# DAPLink.net
KiCad netlist of a schematic drawn in EasyEDA Pro
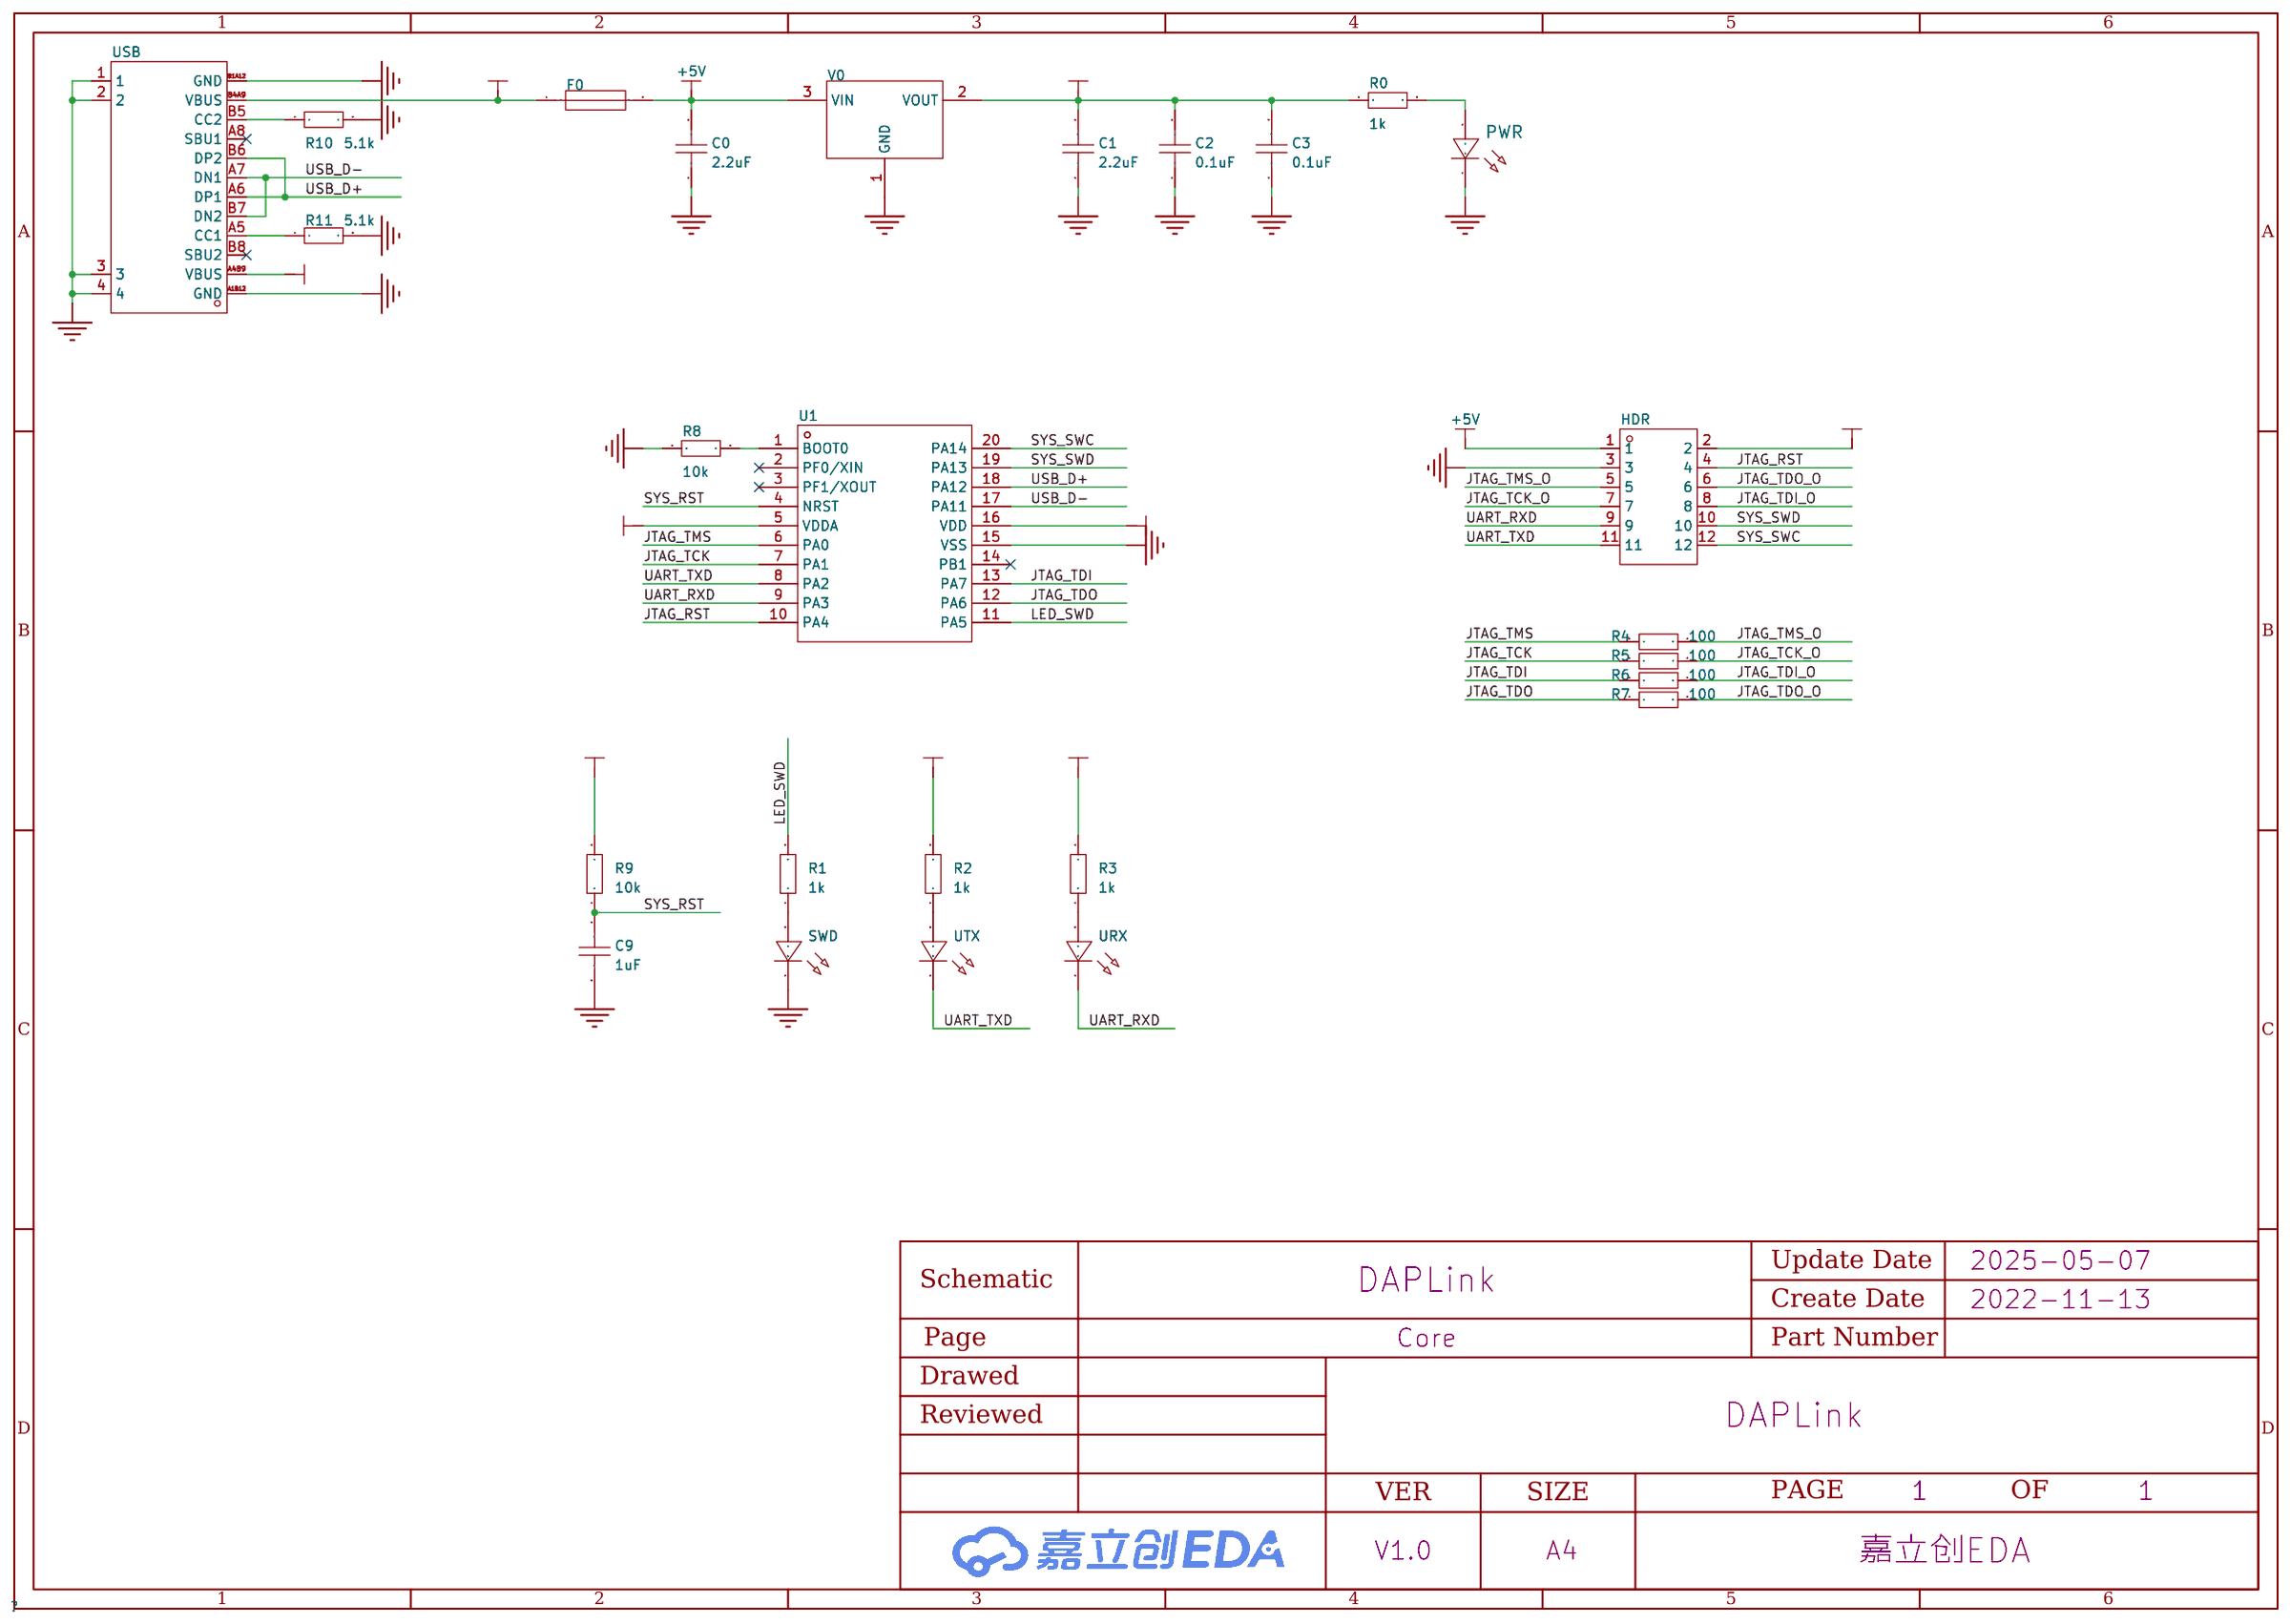
[diagram p0: schematic sheet]

(export (version "E")
  (design (tool "Eeschema 10.0.6"))
  (components
    (comp (ref "C0")
      (value "2.2uF")
      (footprint "easyedapro:C0603")
      (description "容值:100nF;精度:±10%;额定电压:50V;温度系数:X7R;")
      (libsource (lib "easyedapro") (part "C1210X7R475K630NT"))
    )
    (comp (ref "C1")
      (value "2.2uF")
      (footprint "easyedapro:C0603")
      (description "容值:100nF;精度:±10%;额定电压:50V;温度系数:X7R;")
      (libsource (lib "easyedapro") (part "C1210X7R475K630NT"))
    )
    (comp (ref "C2")
      (value "0.1uF")
      (footprint "easyedapro:C0603")
      (description "容值:100nF;精度:±10%;额定电压:50V;温度系数:X7R;")
      (libsource (lib "easyedapro") (part "C1210X7R475K630NT"))
    )
    (comp (ref "C3")
      (value "0.1uF")
      (footprint "easyedapro:C0603")
      (description "容值:100nF;精度:±10%;额定电压:50V;温度系数:X7R;")
      (libsource (lib "easyedapro") (part "C1210X7R475K630NT"))
    )
    (comp (ref "C9")
      (value "1uF")
      (footprint "easyedapro:C0603")
      (description "容值:100nF;精度:±10%;额定电压:50V;温度系数:X7R;")
      (libsource (lib "easyedapro") (part "C1210X7R475K630NT"))
    )
    (comp (ref "F0")
      (value "JK-nSMD050-30")
      (footprint "easyedapro:F1206")
      (description "耐压:30V;最大电流:100A;保持电流(Ih):500mA;跳闸电流:1A;")
      (fields (field (name "Manufacturer") "JK(金科)"))
      (libsource (lib "easyedapro") (part "JK-NSMD050-30V"))
    )
    (comp (ref "HDR")
      (value "~")
      (footprint "easyedapro:HDR-SMD_2X6P-P2.54")
      (libsource (lib "easyedapro") (part "HDR-M-2.54_2x6"))
    )
    (comp (ref "PWR")
      (value "~")
      (footprint "easyedapro:LED_0603")
      (libsource (lib "easyedapro") (part "LED_R"))
    )
    (comp (ref "R0") (value "1k") (footprint "easyedapro:R0603") (libsource (lib "easyedapro") (part "电阻")))
    (comp (ref "R1") (value "1k") (footprint "easyedapro:R0603") (libsource (lib "easyedapro") (part "电阻")))
    (comp (ref "R2") (value "1k") (footprint "easyedapro:R0603") (libsource (lib "easyedapro") (part "电阻")))
    (comp (ref "R3") (value "1k") (footprint "easyedapro:R0603") (libsource (lib "easyedapro") (part "电阻")))
    (comp (ref "R4") (value "100") (footprint "easyedapro:R0603") (libsource (lib "easyedapro") (part "电阻")))
    (comp (ref "R5") (value "100") (footprint "easyedapro:R0603") (libsource (lib "easyedapro") (part "电阻")))
    (comp (ref "R6") (value "100") (footprint "easyedapro:R0603") (libsource (lib "easyedapro") (part "电阻")))
    (comp (ref "R7") (value "100") (footprint "easyedapro:R0603") (libsource (lib "easyedapro") (part "电阻")))
    (comp (ref "R8") (value "10k") (footprint "easyedapro:R0603") (libsource (lib "easyedapro") (part "电阻")))
    (comp (ref "R9") (value "10k") (footprint "easyedapro:R0603") (libsource (lib "easyedapro") (part "电阻")))
    (comp (ref "R10")
      (value "5.1k")
      (footprint "easyedapro:R0603")
      (libsource (lib "easyedapro") (part "电阻"))
    )
    (comp (ref "R11")
      (value "5.1k")
      (footprint "easyedapro:R0603")
      (libsource (lib "easyedapro") (part "电阻"))
    )
    (comp (ref "SWD")
      (value "~")
      (footprint "easyedapro:LED_0603")
      (libsource (lib "easyedapro") (part "LED_B"))
    )
    (comp (ref "U1")
      (value "~")
      (footprint "easyedapro:TSSOP-20_L6.5-W4.4-P0.65-LS6.4-BL")
      (libsource (lib "easyedapro") (part "AT32F425F8"))
    )
    (comp (ref "URX")
      (value "~")
      (footprint "easyedapro:LED_0603")
      (libsource (lib "easyedapro") (part "LED_G"))
    )
    (comp (ref "USB")
      (value "USB-TYPE-C-017")
      (footprint "easyedapro:USB-TYPE-C-SMD_C9900008089")
      (description "连接器类型:Type-C;标准:-;公母:母座;触点数量:16;端口数量:1;安装方式:卧贴;额定电流 - 电源:3A;工作温度范围:-25~+85;")
      (fields (field (name "Manufacturer") "DEALON(德艺隆)"))
      (libsource (lib "easyedapro") (part "USB-TYPE-C-017"))
    )
    (comp (ref "UTX")
      (value "~")
      (footprint "easyedapro:LED_0603")
      (libsource (lib "easyedapro") (part "LED_G"))
    )
    (comp (ref "V0")
      (value "HT7233")
      (footprint "easyedapro:SOT-23-3_L2.9-W1.6-P1.90-LS2.8-BR")
      (fields (field (name "Manufacturer") "HOLTEK(台湾合泰/盛群)"))
      (libsource (lib "easyedapro") (part "HT7233"))
    )
  )
  (nets
    (net (code "1") (name "+3.3V") (class "Default")
      (node (ref "C1") (pin "2") (pinfunction "2_2") (pintype "input"))
      (node (ref "C2") (pin "2") (pinfunction "2_2") (pintype "input"))
      (node (ref "C3") (pin "2") (pinfunction "2_2") (pintype "input"))
      (node (ref "HDR") (pin "2") (pinfunction "2_2") (pintype "input"))
      (node (ref "R0") (pin "1") (pinfunction "1_1") (pintype "input"))
      (node (ref "R2") (pin "2") (pinfunction "2_2") (pintype "input"))
      (node (ref "R3") (pin "2") (pinfunction "2_2") (pintype "input"))
      (node (ref "R9") (pin "2") (pinfunction "2_2") (pintype "input"))
      (node (ref "U1") (pin "16") (pinfunction "VDD_16") (pintype "input"))
      (node (ref "U1") (pin "5") (pinfunction "VDDA_5") (pintype "input"))
      (node (ref "V0") (pin "2") (pinfunction "VOUT_2") (pintype "unspecified"))
    )
    (net (code "2") (name "+5V") (class "Default")
      (node (ref "C0") (pin "2") (pinfunction "2_2") (pintype "input"))
      (node (ref "F0") (pin "2") (pinfunction "2_2") (pintype "unspecified"))
      (node (ref "HDR") (pin "1") (pinfunction "1_1") (pintype "input"))
      (node (ref "V0") (pin "3") (pinfunction "VIN_3") (pintype "unspecified"))
    )
    (net (code "3") (name "/JTAG_RST") (class "Default")
      (node (ref "HDR") (pin "4") (pinfunction "4_4") (pintype "input"))
      (node (ref "U1") (pin "10") (pinfunction "PA4_10") (pintype "input"))
    )
    (net (code "4") (name "/JTAG_TCK") (class "Default")
      (node (ref "R5") (pin "1") (pinfunction "1_1") (pintype "input"))
      (node (ref "U1") (pin "7") (pinfunction "PA1_7") (pintype "input"))
    )
    (net (code "5") (name "/JTAG_TCK_O") (class "Default")
      (node (ref "HDR") (pin "7") (pinfunction "7_7") (pintype "input"))
      (node (ref "R5") (pin "2") (pinfunction "2_2") (pintype "input"))
    )
    (net (code "6") (name "/JTAG_TDI") (class "Default")
      (node (ref "R6") (pin "1") (pinfunction "1_1") (pintype "input"))
      (node (ref "U1") (pin "13") (pinfunction "PA7_13") (pintype "input"))
    )
    (net (code "7") (name "/JTAG_TDI_O") (class "Default")
      (node (ref "HDR") (pin "8") (pinfunction "8_8") (pintype "input"))
      (node (ref "R6") (pin "2") (pinfunction "2_2") (pintype "input"))
    )
    (net (code "8") (name "/JTAG_TDO") (class "Default")
      (node (ref "R7") (pin "1") (pinfunction "1_1") (pintype "input"))
      (node (ref "U1") (pin "12") (pinfunction "PA6_12") (pintype "input"))
    )
    (net (code "9") (name "/JTAG_TDO_O") (class "Default")
      (node (ref "HDR") (pin "6") (pinfunction "6_6") (pintype "input"))
      (node (ref "R7") (pin "2") (pinfunction "2_2") (pintype "input"))
    )
    (net (code "10") (name "/JTAG_TMS") (class "Default")
      (node (ref "R4") (pin "1") (pinfunction "1_1") (pintype "input"))
      (node (ref "U1") (pin "6") (pinfunction "PA0_6") (pintype "input"))
    )
    (net (code "11") (name "/JTAG_TMS_O") (class "Default")
      (node (ref "HDR") (pin "5") (pinfunction "5_5") (pintype "input"))
      (node (ref "R4") (pin "2") (pinfunction "2_2") (pintype "input"))
    )
    (net (code "12") (name "/LED_SWD") (class "Default")
      (node (ref "R1") (pin "2") (pinfunction "2_2") (pintype "input"))
      (node (ref "U1") (pin "11") (pinfunction "PA5_11") (pintype "input"))
    )
    (net (code "13") (name "/SYS_RST") (class "Default")
      (node (ref "C9") (pin "1") (pinfunction "1_1") (pintype "input"))
      (node (ref "R9") (pin "1") (pinfunction "1_1") (pintype "input"))
      (node (ref "U1") (pin "4") (pinfunction "NRST_4") (pintype "input"))
    )
    (net (code "14") (name "/SYS_SWC") (class "Default")
      (node (ref "HDR") (pin "12") (pinfunction "12_12") (pintype "input"))
      (node (ref "U1") (pin "20") (pinfunction "PA14_20") (pintype "input"))
    )
    (net (code "15") (name "/SYS_SWD") (class "Default")
      (node (ref "HDR") (pin "10") (pinfunction "10_10") (pintype "input"))
      (node (ref "U1") (pin "19") (pinfunction "PA13_19") (pintype "input"))
    )
    (net (code "16") (name "/UART_RXD") (class "Default")
      (node (ref "HDR") (pin "9") (pinfunction "9_9") (pintype "input"))
      (node (ref "U1") (pin "9") (pinfunction "PA3_9") (pintype "input"))
      (node (ref "URX") (pin "1") (pinfunction "C_1") (pintype "input"))
    )
    (net (code "17") (name "/UART_TXD") (class "Default")
      (node (ref "HDR") (pin "11") (pinfunction "11_11") (pintype "input"))
      (node (ref "U1") (pin "8") (pinfunction "PA2_8") (pintype "input"))
      (node (ref "UTX") (pin "1") (pinfunction "C_1") (pintype "input"))
    )
    (net (code "18") (name "/USB_D+") (class "Default")
      (node (ref "U1") (pin "18") (pinfunction "PA12_18") (pintype "input"))
      (node (ref "USB") (pin "A6") (pinfunction "DP1_A6") (pintype "input"))
      (node (ref "USB") (pin "B6") (pinfunction "DP2_B6") (pintype "input"))
    )
    (net (code "19") (name "/USB_D-") (class "Default")
      (node (ref "U1") (pin "17") (pinfunction "PA11_17") (pintype "input"))
      (node (ref "USB") (pin "A7") (pinfunction "DN1_A7") (pintype "input"))
      (node (ref "USB") (pin "B7") (pinfunction "DN2_B7") (pintype "input"))
    )
    (net (code "20") (name "GND") (class "Default")
      (node (ref "C0") (pin "1") (pinfunction "1_1") (pintype "input"))
      (node (ref "C1") (pin "1") (pinfunction "1_1") (pintype "input"))
      (node (ref "C2") (pin "1") (pinfunction "1_1") (pintype "input"))
      (node (ref "C3") (pin "1") (pinfunction "1_1") (pintype "input"))
      (node (ref "C9") (pin "2") (pinfunction "2_2") (pintype "input"))
      (node (ref "HDR") (pin "3") (pinfunction "3_3") (pintype "input"))
      (node (ref "PWR") (pin "1") (pinfunction "C_1") (pintype "input"))
      (node (ref "R10") (pin "2") (pinfunction "2_2") (pintype "input"))
      (node (ref "R11") (pin "2") (pinfunction "2_2") (pintype "input"))
      (node (ref "R8") (pin "1") (pinfunction "1_1") (pintype "input"))
      (node (ref "SWD") (pin "1") (pinfunction "C_1") (pintype "input"))
      (node (ref "U1") (pin "15") (pinfunction "VSS_15") (pintype "input"))
      (node (ref "USB") (pin "1") (pinfunction "1_1") (pintype "input"))
      (node (ref "USB") (pin "2") (pinfunction "2_2") (pintype "input"))
      (node (ref "USB") (pin "3") (pinfunction "3_3") (pintype "input"))
      (node (ref "USB") (pin "4") (pinfunction "4_4") (pintype "input"))
      (node (ref "USB") (pin "A1B12") (pinfunction "GND_A1B12") (pintype "input"))
      (node (ref "USB") (pin "B1A12") (pinfunction "GND_B1A12") (pintype "input"))
      (node (ref "V0") (pin "1") (pinfunction "GND_1") (pintype "unspecified"))
    )
    (net (code "21") (name "Net-(PWR-A)") (class "Default")
      (node (ref "PWR") (pin "2") (pinfunction "A_2") (pintype "input"))
      (node (ref "R0") (pin "2") (pinfunction "2_2") (pintype "input"))
    )
    (net (code "22") (name "Net-(SWD-A)") (class "Default")
      (node (ref "R1") (pin "1") (pinfunction "1_1") (pintype "input"))
      (node (ref "SWD") (pin "2") (pinfunction "A_2") (pintype "input"))
    )
    (net (code "23") (name "Net-(U1-BOOT0)") (class "Default")
      (node (ref "R8") (pin "2") (pinfunction "2_2") (pintype "input"))
      (node (ref "U1") (pin "1") (pinfunction "BOOT0_1") (pintype "input"))
    )
    (net (code "24") (name "Net-(URX-A)") (class "Default")
      (node (ref "R3") (pin "1") (pinfunction "1_1") (pintype "input"))
      (node (ref "URX") (pin "2") (pinfunction "A_2") (pintype "input"))
    )
    (net (code "25") (name "Net-(USB-CC1)") (class "Default")
      (node (ref "R11") (pin "1") (pinfunction "1_1") (pintype "input"))
      (node (ref "USB") (pin "A5") (pinfunction "CC1_A5") (pintype "input"))
    )
    (net (code "26") (name "Net-(USB-CC2)") (class "Default")
      (node (ref "R10") (pin "1") (pinfunction "1_1") (pintype "input"))
      (node (ref "USB") (pin "B5") (pinfunction "CC2_B5") (pintype "input"))
    )
    (net (code "27") (name "Net-(UTX-A)") (class "Default")
      (node (ref "R2") (pin "1") (pinfunction "1_1") (pintype "input"))
      (node (ref "UTX") (pin "2") (pinfunction "A_2") (pintype "input"))
    )
    (net (code "28") (name "VBUS") (class "Default")
      (node (ref "F0") (pin "1") (pinfunction "1_1") (pintype "unspecified"))
      (node (ref "USB") (pin "A4B9") (pinfunction "VBUS_A4B9") (pintype "input"))
      (node (ref "USB") (pin "B4A9") (pinfunction "VBUS_B4A9") (pintype "input"))
    )
    (net (code "29") (name "unconnected-(U1-PB1-Pad14)") (class "Default")
      (node (ref "U1") (pin "14") (pinfunction "PB1_14") (pintype "input+no_connect"))
    )
    (net (code "30") (name "unconnected-(U1-PF0{slash}XIN-Pad2)") (class "Default")
      (node (ref "U1") (pin "2") (pinfunction "PF0/XIN_2") (pintype "input+no_connect"))
    )
    (net (code "31") (name "unconnected-(U1-PF1{slash}XOUT-Pad3)") (class "Default")
      (node (ref "U1") (pin "3") (pinfunction "PF1/XOUT_3") (pintype "input+no_connect"))
    )
    (net (code "32") (name "unconnected-(USB-SBU1-PadA8)") (class "Default")
      (node (ref "USB") (pin "A8") (pinfunction "SBU1_A8") (pintype "input+no_connect"))
    )
    (net (code "33") (name "unconnected-(USB-SBU2-PadB8)") (class "Default")
      (node (ref "USB") (pin "B8") (pinfunction "SBU2_B8") (pintype "input+no_connect"))
    )
  )
)
